# K22F_Shield.net
KiCad netlist of a schematic drawn in Altium Designer
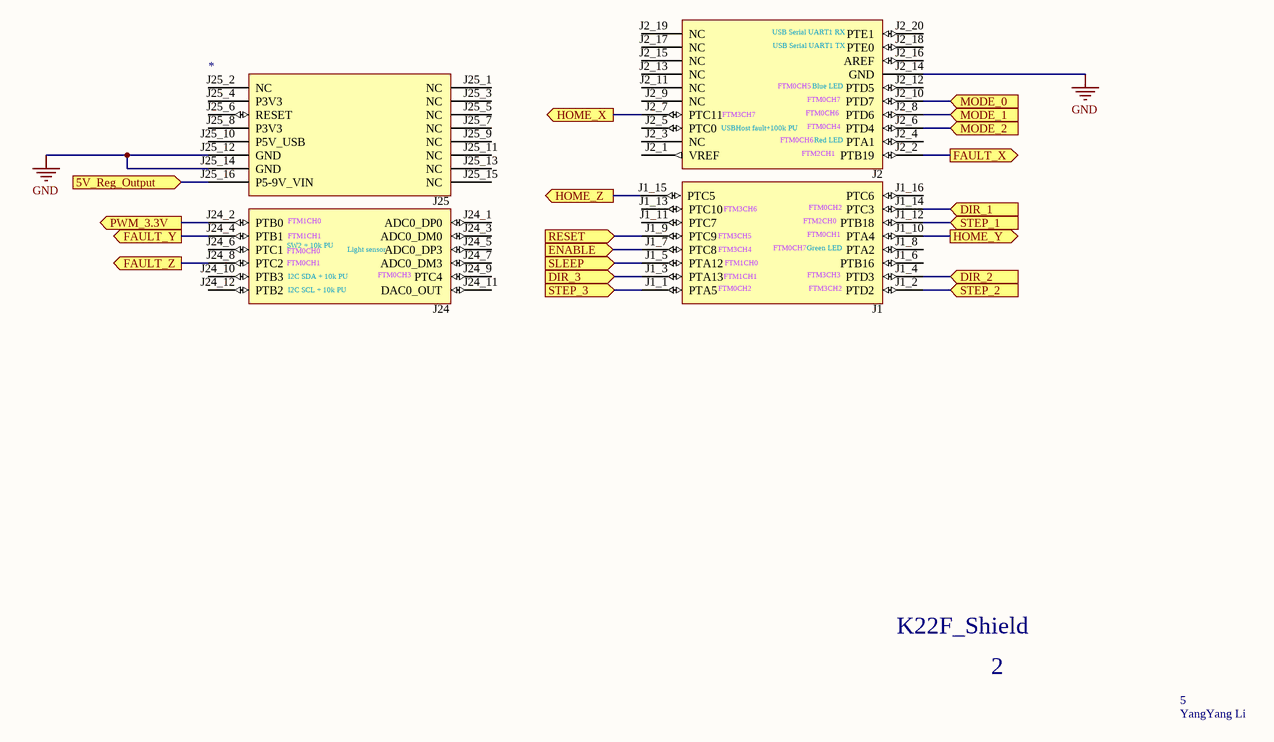
[diagram p0: K22F_Shield.SchDoc]

(export (version "E")
  (design (tool "Eeschema 10.0.6"))
  (components
    (comp (ref "*1") (value "*") (footprint "FRDM-K22F") (libsource (lib "*") (part "NXP FRDM-K22F")))
  )
  (nets
    (net (code "1") (name "/5V_Reg_Output") (class "Default")
      (node (ref "*1") (pin "J25_16") (pinfunction "P5-9V_VIN_J25_16") (pintype "power_in"))
    )
    (net (code "2") (name "/DIR_1") (class "Default")
      (node (ref "*1") (pin "J1_14") (pinfunction "PTC3_J1_14") (pintype "bidirectional"))
    )
    (net (code "3") (name "/DIR_2") (class "Default")
      (node (ref "*1") (pin "J1_4") (pinfunction "PTD3_J1_4") (pintype "bidirectional"))
    )
    (net (code "4") (name "/DIR_3") (class "Default")
      (node (ref "*1") (pin "J1_3") (pinfunction "PTA13_J1_3") (pintype "bidirectional"))
    )
    (net (code "5") (name "/ENABLE") (class "Default")
      (node (ref "*1") (pin "J1_7") (pinfunction "PTC8_J1_7") (pintype "bidirectional"))
    )
    (net (code "6") (name "/FAULT_X") (class "Default")
      (node (ref "*1") (pin "J2_2") (pinfunction "PTB19_J2_2") (pintype "bidirectional"))
    )
    (net (code "7") (name "/FAULT_Y") (class "Default")
      (node (ref "*1") (pin "J24_4") (pinfunction "PTB1_J24_4") (pintype "bidirectional"))
    )
    (net (code "8") (name "/FAULT_Z") (class "Default")
      (node (ref "*1") (pin "J24_8") (pinfunction "PTC2_J24_8") (pintype "bidirectional"))
    )
    (net (code "9") (name "/HOME_X") (class "Default")
      (node (ref "*1") (pin "J2_7") (pinfunction "PTC11_J2_7") (pintype "bidirectional"))
    )
    (net (code "10") (name "/HOME_Y") (class "Default")
      (node (ref "*1") (pin "J1_10") (pinfunction "PTA4_J1_10") (pintype "bidirectional"))
    )
    (net (code "11") (name "/HOME_Z") (class "Default")
      (node (ref "*1") (pin "J1_15") (pinfunction "PTC5_J1_15") (pintype "bidirectional"))
    )
    (net (code "12") (name "/MODE_0") (class "Default")
      (node (ref "*1") (pin "J2_10") (pinfunction "PTD7_J2_10") (pintype "bidirectional"))
    )
    (net (code "13") (name "/MODE_1") (class "Default")
      (node (ref "*1") (pin "J2_8") (pinfunction "PTD6_J2_8") (pintype "bidirectional"))
    )
    (net (code "14") (name "/MODE_2") (class "Default")
      (node (ref "*1") (pin "J2_6") (pinfunction "PTD4_J2_6") (pintype "bidirectional"))
    )
    (net (code "15") (name "/PWM_3.3V") (class "Default")
      (node (ref "*1") (pin "J24_2") (pinfunction "PTB0_J24_2") (pintype "bidirectional"))
    )
    (net (code "16") (name "/RESET") (class "Default")
      (node (ref "*1") (pin "J1_9") (pinfunction "PTC9_J1_9") (pintype "bidirectional"))
    )
    (net (code "17") (name "/SLEEP") (class "Default")
      (node (ref "*1") (pin "J1_5") (pinfunction "PTA12_J1_5") (pintype "bidirectional"))
    )
    (net (code "18") (name "/STEP_1") (class "Default")
      (node (ref "*1") (pin "J1_12") (pinfunction "PTB18_J1_12") (pintype "bidirectional"))
    )
    (net (code "19") (name "/STEP_2") (class "Default")
      (node (ref "*1") (pin "J1_2") (pinfunction "PTD2_J1_2") (pintype "bidirectional"))
    )
    (net (code "20") (name "/STEP_3") (class "Default")
      (node (ref "*1") (pin "J1_1") (pinfunction "PTA5_J1_1") (pintype "bidirectional"))
    )
    (net (code "21") (name "GND") (class "Default")
      (node (ref "*1") (pin "J25_12") (pinfunction "GND_J25_12") (pintype "power_in"))
      (node (ref "*1") (pin "J25_14") (pinfunction "GND_J25_14") (pintype "power_in"))
      (node (ref "*1") (pin "J2_14") (pinfunction "GND_J2_14") (pintype "power_in"))
    )
    (net (code "22") (name "unconnected-(*1-ADC0_DM0-PadJ24_3)") (class "Default")
      (node (ref "*1") (pin "J24_3") (pinfunction "ADC0_DM0_J24_3") (pintype "bidirectional"))
    )
    (net (code "23") (name "unconnected-(*1-ADC0_DM3-PadJ24_7)") (class "Default")
      (node (ref "*1") (pin "J24_7") (pinfunction "ADC0_DM3_J24_7") (pintype "bidirectional"))
    )
    (net (code "24") (name "unconnected-(*1-ADC0_DP0-PadJ24_1)") (class "Default")
      (node (ref "*1") (pin "J24_1") (pinfunction "ADC0_DP0_J24_1") (pintype "bidirectional"))
    )
    (net (code "25") (name "unconnected-(*1-ADC0_DP3-PadJ24_5)") (class "Default")
      (node (ref "*1") (pin "J24_5") (pinfunction "ADC0_DP3_J24_5") (pintype "bidirectional"))
    )
    (net (code "26") (name "unconnected-(*1-AREF-PadJ2_16)") (class "Default")
      (node (ref "*1") (pin "J2_16") (pinfunction "AREF_J2_16") (pintype "bidirectional"))
    )
    (net (code "27") (name "unconnected-(*1-DAC0_OUT-PadJ24_11)") (class "Default")
      (node (ref "*1") (pin "J24_11") (pinfunction "DAC0_OUT_J24_11") (pintype "bidirectional"))
    )
    (net (code "28") (name "unconnected-(*1-NC-PadJ2_3)") (class "Default")
      (node (ref "*1") (pin "J2_3") (pinfunction "NC_J2_3") (pintype "passive"))
    )
    (net (code "29") (name "unconnected-(*1-NC-PadJ2_9)") (class "Default")
      (node (ref "*1") (pin "J2_9") (pinfunction "NC_J2_9") (pintype "passive"))
    )
    (net (code "30") (name "unconnected-(*1-NC-PadJ2_11)") (class "Default")
      (node (ref "*1") (pin "J2_11") (pinfunction "NC_J2_11") (pintype "passive"))
    )
    (net (code "31") (name "unconnected-(*1-NC-PadJ2_13)") (class "Default")
      (node (ref "*1") (pin "J2_13") (pinfunction "NC_J2_13") (pintype "passive"))
    )
    (net (code "32") (name "unconnected-(*1-NC-PadJ2_15)") (class "Default")
      (node (ref "*1") (pin "J2_15") (pinfunction "NC_J2_15") (pintype "passive"))
    )
    (net (code "33") (name "unconnected-(*1-NC-PadJ2_17)") (class "Default")
      (node (ref "*1") (pin "J2_17") (pinfunction "NC_J2_17") (pintype "passive"))
    )
    (net (code "34") (name "unconnected-(*1-NC-PadJ2_19)") (class "Default")
      (node (ref "*1") (pin "J2_19") (pinfunction "NC_J2_19") (pintype "passive"))
    )
    (net (code "35") (name "unconnected-(*1-NC-PadJ25_1)") (class "Default")
      (node (ref "*1") (pin "J25_1") (pinfunction "NC_J25_1") (pintype "passive"))
    )
    (net (code "36") (name "unconnected-(*1-NC-PadJ25_2)") (class "Default")
      (node (ref "*1") (pin "J25_2") (pinfunction "NC_J25_2") (pintype "passive"))
    )
    (net (code "37") (name "unconnected-(*1-NC-PadJ25_3)") (class "Default")
      (node (ref "*1") (pin "J25_3") (pinfunction "NC_J25_3") (pintype "passive"))
    )
    (net (code "38") (name "unconnected-(*1-NC-PadJ25_5)") (class "Default")
      (node (ref "*1") (pin "J25_5") (pinfunction "NC_J25_5") (pintype "passive"))
    )
    (net (code "39") (name "unconnected-(*1-NC-PadJ25_7)") (class "Default")
      (node (ref "*1") (pin "J25_7") (pinfunction "NC_J25_7") (pintype "passive"))
    )
    (net (code "40") (name "unconnected-(*1-NC-PadJ25_9)") (class "Default")
      (node (ref "*1") (pin "J25_9") (pinfunction "NC_J25_9") (pintype "passive"))
    )
    (net (code "41") (name "unconnected-(*1-NC-PadJ25_11)") (class "Default")
      (node (ref "*1") (pin "J25_11") (pinfunction "NC_J25_11") (pintype "passive"))
    )
    (net (code "42") (name "unconnected-(*1-NC-PadJ25_13)") (class "Default")
      (node (ref "*1") (pin "J25_13") (pinfunction "NC_J25_13") (pintype "passive"))
    )
    (net (code "43") (name "unconnected-(*1-NC-PadJ25_15)") (class "Default")
      (node (ref "*1") (pin "J25_15") (pinfunction "NC_J25_15") (pintype "passive"))
    )
    (net (code "44") (name "unconnected-(*1-P3V3-PadJ25_4)") (class "Default")
      (node (ref "*1") (pin "J25_4") (pinfunction "P3V3_J25_4") (pintype "power_in"))
    )
    (net (code "45") (name "unconnected-(*1-P3V3-PadJ25_8)") (class "Default")
      (node (ref "*1") (pin "J25_8") (pinfunction "P3V3_J25_8") (pintype "power_in"))
    )
    (net (code "46") (name "unconnected-(*1-P5V_USB-PadJ25_10)") (class "Default")
      (node (ref "*1") (pin "J25_10") (pinfunction "P5V_USB_J25_10") (pintype "power_in"))
    )
    (net (code "47") (name "unconnected-(*1-PTA1-PadJ2_4)") (class "Default")
      (node (ref "*1") (pin "J2_4") (pinfunction "PTA1_J2_4") (pintype "bidirectional"))
    )
    (net (code "48") (name "unconnected-(*1-PTA2-PadJ1_8)") (class "Default")
      (node (ref "*1") (pin "J1_8") (pinfunction "PTA2_J1_8") (pintype "bidirectional"))
    )
    (net (code "49") (name "unconnected-(*1-PTB2-PadJ24_12)") (class "Default")
      (node (ref "*1") (pin "J24_12") (pinfunction "PTB2_J24_12") (pintype "bidirectional"))
    )
    (net (code "50") (name "unconnected-(*1-PTB3-PadJ24_10)") (class "Default")
      (node (ref "*1") (pin "J24_10") (pinfunction "PTB3_J24_10") (pintype "bidirectional"))
    )
    (net (code "51") (name "unconnected-(*1-PTB16-PadJ1_6)") (class "Default")
      (node (ref "*1") (pin "J1_6") (pinfunction "PTB16_J1_6") (pintype "bidirectional"))
    )
    (net (code "52") (name "unconnected-(*1-PTC0-PadJ2_5)") (class "Default")
      (node (ref "*1") (pin "J2_5") (pinfunction "PTC0_J2_5") (pintype "bidirectional"))
    )
    (net (code "53") (name "unconnected-(*1-PTC1-PadJ24_6)") (class "Default")
      (node (ref "*1") (pin "J24_6") (pinfunction "PTC1_J24_6") (pintype "bidirectional"))
    )
    (net (code "54") (name "unconnected-(*1-PTC4-PadJ24_9)") (class "Default")
      (node (ref "*1") (pin "J24_9") (pinfunction "PTC4_J24_9") (pintype "bidirectional"))
    )
    (net (code "55") (name "unconnected-(*1-PTC6-PadJ1_16)") (class "Default")
      (node (ref "*1") (pin "J1_16") (pinfunction "PTC6_J1_16") (pintype "bidirectional"))
    )
    (net (code "56") (name "unconnected-(*1-PTC7-PadJ1_11)") (class "Default")
      (node (ref "*1") (pin "J1_11") (pinfunction "PTC7_J1_11") (pintype "bidirectional"))
    )
    (net (code "57") (name "unconnected-(*1-PTC10-PadJ1_13)") (class "Default")
      (node (ref "*1") (pin "J1_13") (pinfunction "PTC10_J1_13") (pintype "bidirectional"))
    )
    (net (code "58") (name "unconnected-(*1-PTD5-PadJ2_12)") (class "Default")
      (node (ref "*1") (pin "J2_12") (pinfunction "PTD5_J2_12") (pintype "bidirectional"))
    )
    (net (code "59") (name "unconnected-(*1-PTE0-PadJ2_18)") (class "Default")
      (node (ref "*1") (pin "J2_18") (pinfunction "PTE0_J2_18") (pintype "bidirectional"))
    )
    (net (code "60") (name "unconnected-(*1-PTE1-PadJ2_20)") (class "Default")
      (node (ref "*1") (pin "J2_20") (pinfunction "PTE1_J2_20") (pintype "bidirectional"))
    )
    (net (code "61") (name "unconnected-(*1-RESET-PadJ25_6)") (class "Default")
      (node (ref "*1") (pin "J25_6") (pinfunction "RESET_J25_6") (pintype "bidirectional"))
    )
    (net (code "62") (name "unconnected-(*1-VREF-PadJ2_1)") (class "Default")
      (node (ref "*1") (pin "J2_1") (pinfunction "VREF_J2_1") (pintype "output"))
    )
  )
)
